# DRV8835_Breakout.net
KiCad netlist of a schematic drawn in EAGLE
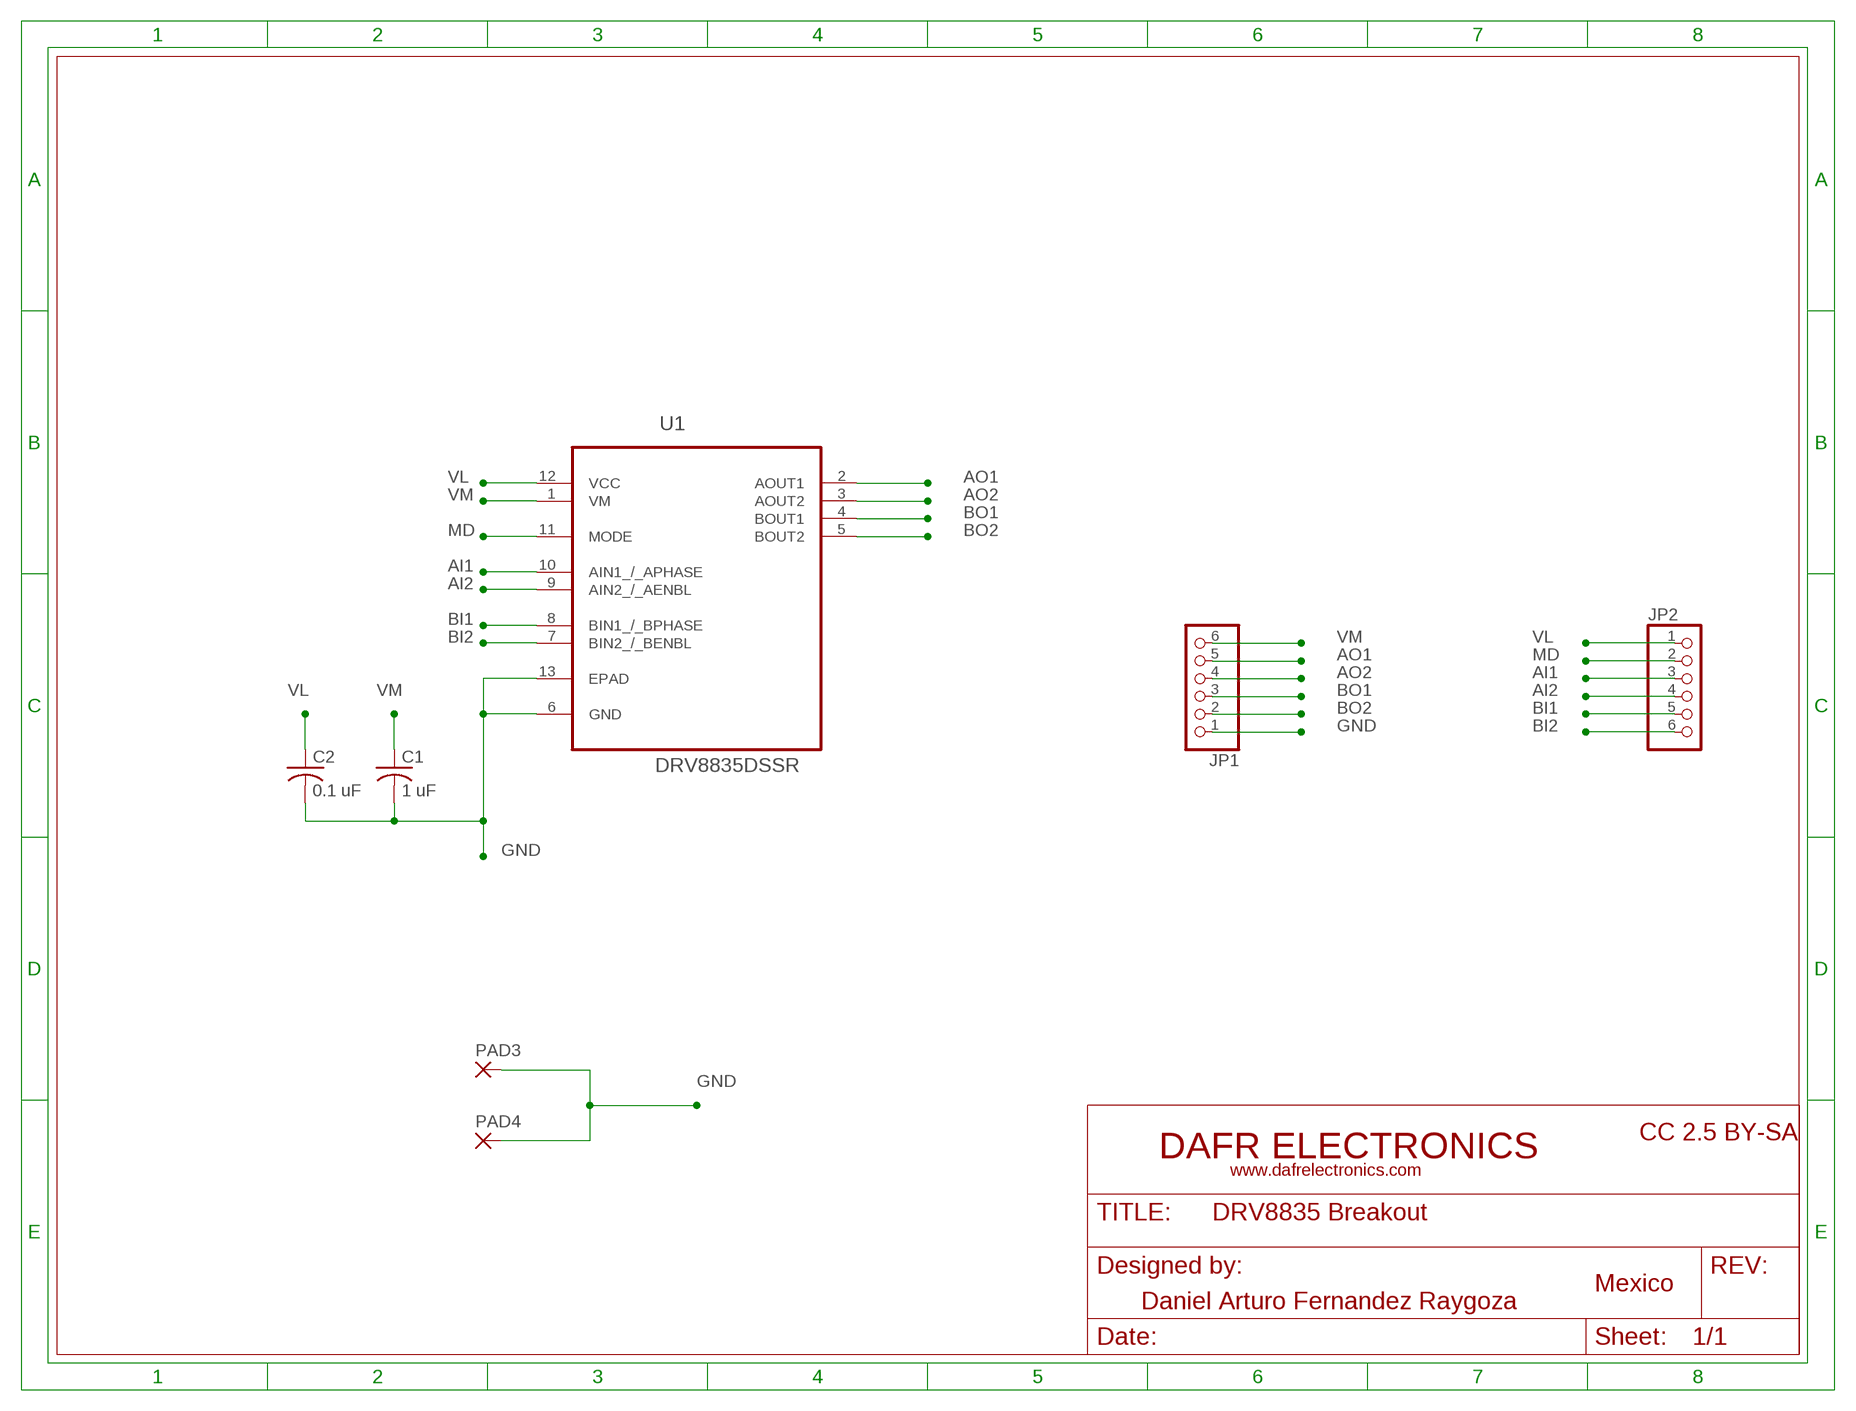
[diagram p0: schematic, sheet 1]

(export (version "E")
  (design (tool "Eeschema 10.0.6"))
  (components
    (comp (ref "C1")
      (value "1 uF")
      (footprint "eagle-import:C0603K")
      (libsource (lib "eagle-import") (part "C-USC0603K"))
    )
    (comp (ref "C2")
      (value "0.1 uF")
      (footprint "eagle-import:C0603K")
      (libsource (lib "eagle-import") (part "C-USC0603K"))
    )
    (comp (ref "JP1")
      (value "PINHD-1X6CLEAN")
      (footprint "eagle-import:1X06-CLEAN")
      (libsource (lib "eagle-import") (part "PINHD-1X6CLEAN"))
    )
    (comp (ref "JP2")
      (value "PINHD-1X6CLEAN")
      (footprint "eagle-import:1X06-CLEAN")
      (libsource (lib "eagle-import") (part "PINHD-1X6CLEAN"))
    )
    (comp (ref "PAD3")
      (value "SMD2")
      (footprint "eagle-import:SMD1,27-2,54")
      (libsource (lib "eagle-import") (part "SMD2"))
    )
    (comp (ref "PAD4")
      (value "SMD2")
      (footprint "eagle-import:SMD1,27-2,54")
      (libsource (lib "eagle-import") (part "SMD2"))
    )
    (comp (ref "U1")
      (value "DRV8835DSSR")
      (footprint "eagle-import:SON50P200X300X80-13N")
      (fields (field (name "MPN") "DRV8835DSSR "))
      (libsource (lib "eagle-import") (part "DRV8835DSSR"))
    )
  )
  (nets
    (net (code "1") (name "/AI1") (class "Default")
      (node (ref "JP2") (pin "3") (pinfunction "3_3") (pintype "passive"))
      (node (ref "U1") (pin "10") (pinfunction "AIN1_/_APHASE_10") (pintype "input"))
    )
    (net (code "2") (name "/AI2") (class "Default")
      (node (ref "JP2") (pin "4") (pinfunction "4_4") (pintype "passive"))
      (node (ref "U1") (pin "9") (pinfunction "AIN2_/_AENBL_9") (pintype "input"))
    )
    (net (code "3") (name "/AO1") (class "Default")
      (node (ref "JP1") (pin "5") (pinfunction "5_5") (pintype "passive"))
      (node (ref "U1") (pin "2") (pinfunction "AOUT1_2") (pintype "output"))
    )
    (net (code "4") (name "/AO2") (class "Default")
      (node (ref "JP1") (pin "4") (pinfunction "4_4") (pintype "passive"))
      (node (ref "U1") (pin "3") (pinfunction "AOUT2_3") (pintype "output"))
    )
    (net (code "5") (name "/BI1") (class "Default")
      (node (ref "JP2") (pin "5") (pinfunction "5_5") (pintype "passive"))
      (node (ref "U1") (pin "8") (pinfunction "BIN1_/_BPHASE_8") (pintype "input"))
    )
    (net (code "6") (name "/BI2") (class "Default")
      (node (ref "JP2") (pin "6") (pinfunction "6_6") (pintype "passive"))
      (node (ref "U1") (pin "7") (pinfunction "BIN2_/_BENBL_7") (pintype "input"))
    )
    (net (code "7") (name "/BO1") (class "Default")
      (node (ref "JP1") (pin "3") (pinfunction "3_3") (pintype "passive"))
      (node (ref "U1") (pin "4") (pinfunction "BOUT1_4") (pintype "output"))
    )
    (net (code "8") (name "/BO2") (class "Default")
      (node (ref "JP1") (pin "2") (pinfunction "2_2") (pintype "passive"))
      (node (ref "U1") (pin "5") (pinfunction "BOUT2_5") (pintype "output"))
    )
    (net (code "9") (name "/GND") (class "Default")
      (node (ref "C1") (pin "2") (pinfunction "2_2") (pintype "passive"))
      (node (ref "C2") (pin "2") (pinfunction "2_2") (pintype "passive"))
      (node (ref "JP1") (pin "1") (pinfunction "1_1") (pintype "passive"))
      (node (ref "PAD3") (pin "1") (pinfunction "P_1") (pintype "passive"))
      (node (ref "PAD4") (pin "1") (pinfunction "P_1") (pintype "passive"))
      (node (ref "U1") (pin "13") (pinfunction "EPAD_13") (pintype "passive"))
      (node (ref "U1") (pin "6") (pinfunction "GND_6") (pintype "passive"))
    )
    (net (code "10") (name "/MD") (class "Default")
      (node (ref "JP2") (pin "2") (pinfunction "2_2") (pintype "passive"))
      (node (ref "U1") (pin "11") (pinfunction "MODE_11") (pintype "input"))
    )
    (net (code "11") (name "/VL") (class "Default")
      (node (ref "C2") (pin "1") (pinfunction "1_1") (pintype "passive"))
      (node (ref "JP2") (pin "1") (pinfunction "1_1") (pintype "passive"))
      (node (ref "U1") (pin "12") (pinfunction "VCC_12") (pintype "power_in"))
    )
    (net (code "12") (name "/VM") (class "Default")
      (node (ref "C1") (pin "1") (pinfunction "1_1") (pintype "passive"))
      (node (ref "JP1") (pin "6") (pinfunction "6_6") (pintype "passive"))
      (node (ref "U1") (pin "1") (pinfunction "VM_1") (pintype "power_in"))
    )
  )
)
